# magspoof.net
KiCad netlist of a schematic drawn in EAGLE
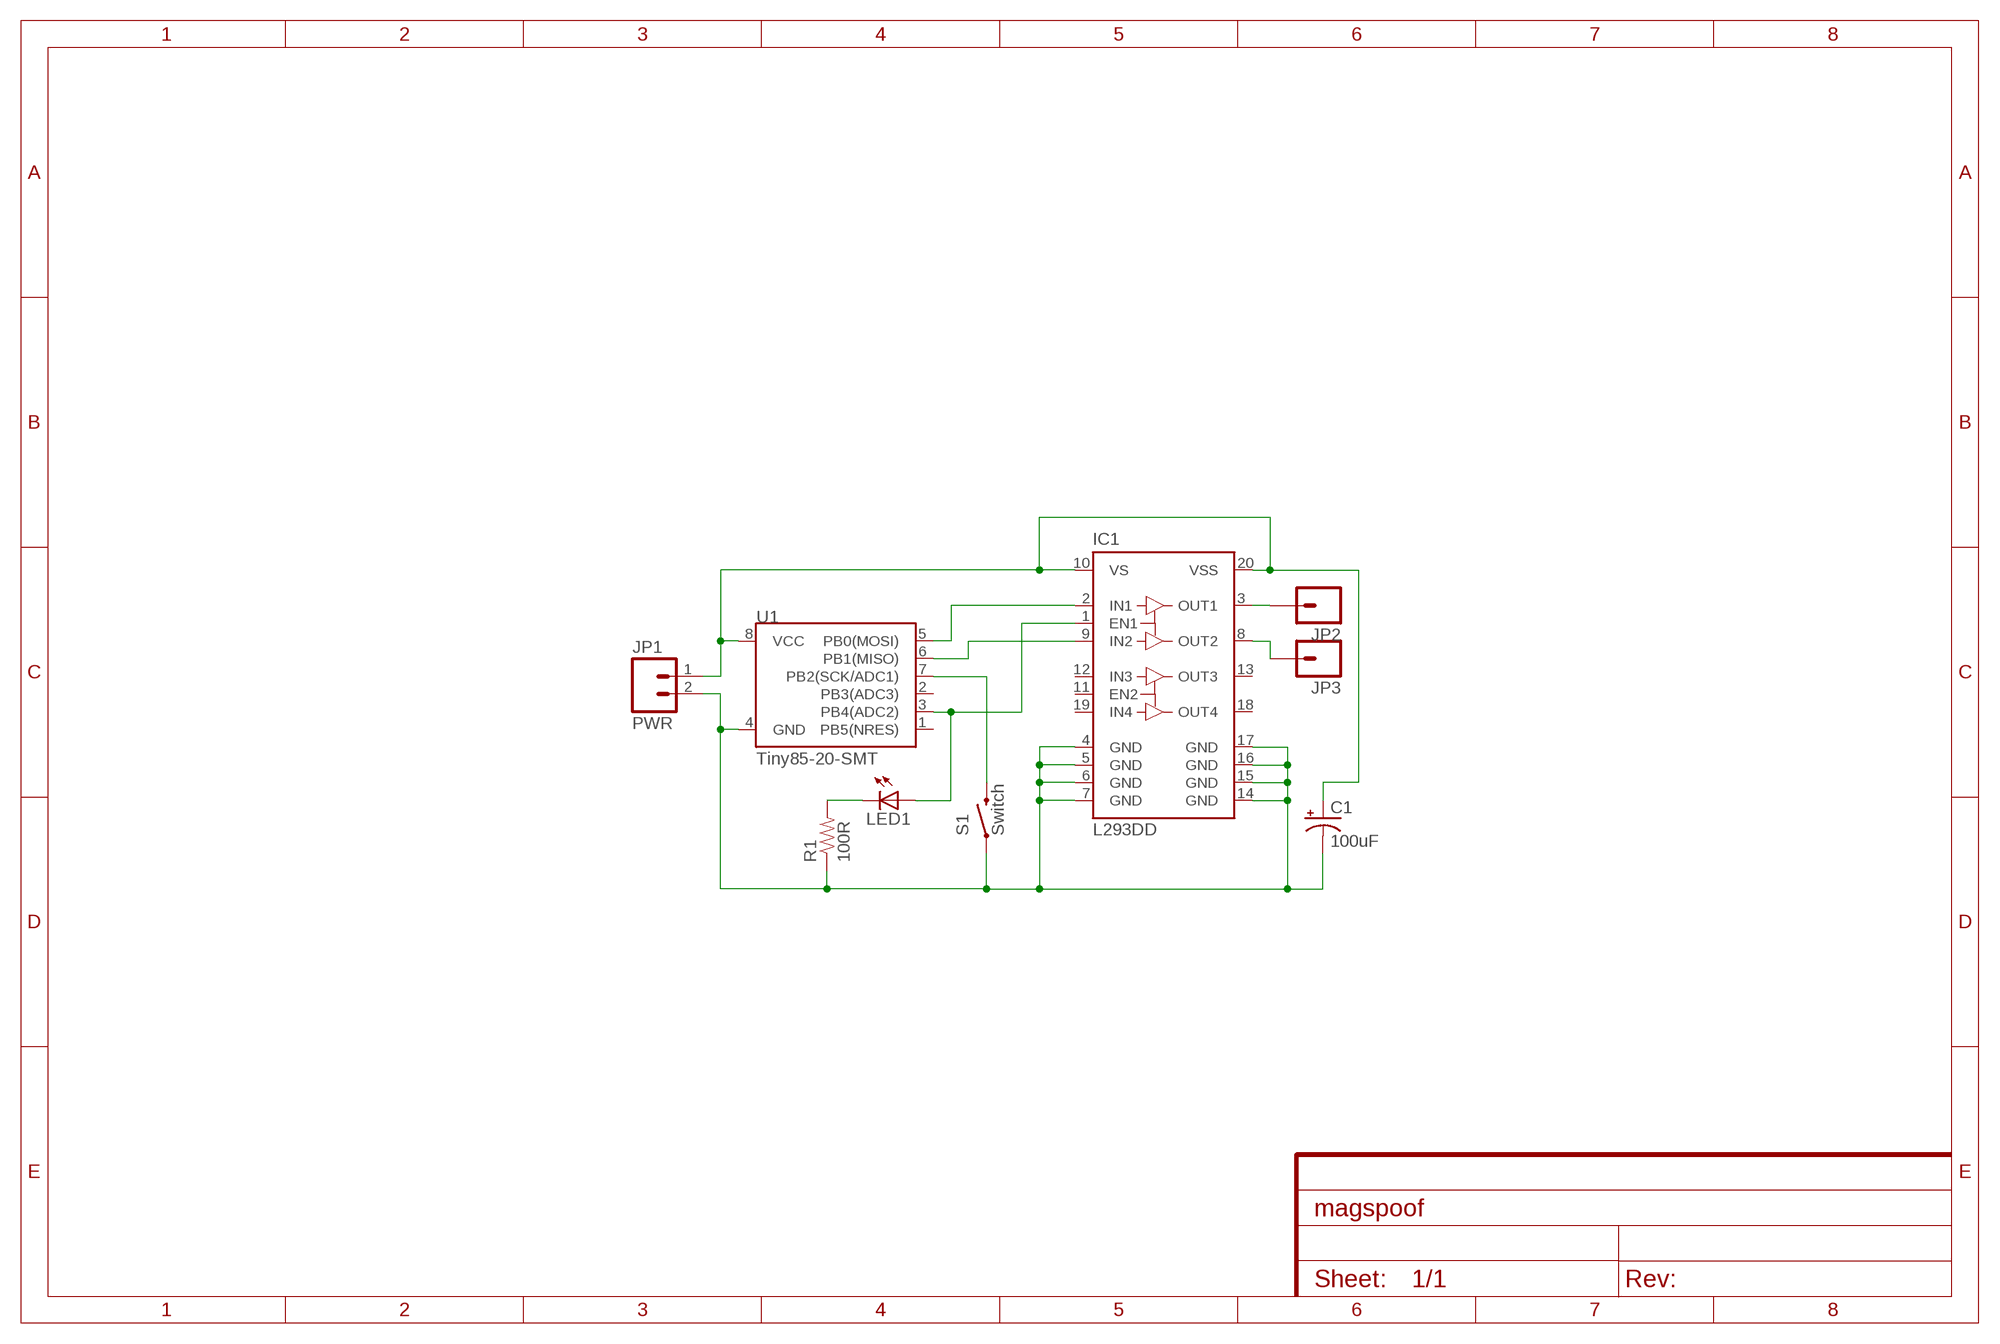
[diagram p0: schematic, sheet 1]

(export (version "E")
  (design (tool "Eeschema 10.0.6"))
  (components
    (comp (ref "C1")
      (value "100uF")
      (footprint "eagle-import:NIC_10X10.5_CAP")
      (libsource (lib "eagle-import") (part "100UF-63V-20%(ELECT)"))
    )
    (comp (ref "IC1")
      (value "L293DD")
      (footprint "eagle-import:SO20")
      (libsource (lib "eagle-import") (part "L293DD"))
    )
    (comp (ref "JP1")
      (value "PWR")
      (footprint "eagle-import:JST-2-SMD")
      (libsource (lib "eagle-import") (part "M02-JST-2MM-SMT"))
    )
    (comp (ref "JP2")
      (value "M01SMDNS")
      (footprint "eagle-import:1X01NS")
      (libsource (lib "eagle-import") (part "M01SMDNS"))
    )
    (comp (ref "JP3")
      (value "M01SMDNS")
      (footprint "eagle-import:1X01NS")
      (libsource (lib "eagle-import") (part "M01SMDNS"))
    )
    (comp (ref "LED1")
      (value "LEDCHIP-LED0805")
      (footprint "eagle-import:CHIP-LED0805")
      (libsource (lib "eagle-import") (part "LEDCHIP-LED0805"))
    )
    (comp (ref "R1")
      (value "100R")
      (footprint "eagle-import:0603-RES")
      (libsource (lib "eagle-import") (part "RESISTOR0603-RES"))
    )
    (comp (ref "S1")
      (value "Switch")
      (footprint "eagle-import:TACTILE-SWITCH-SMD")
      (libsource (lib "eagle-import") (part "SWITCH-MOMENTARY-2SMD-REDUNDANT"))
    )
    (comp (ref "U1")
      (value "Tiny85-20-SMT")
      (footprint "eagle-import:SO08-EIAJ")
      (libsource (lib "eagle-import") (part "ATTINY45TINY85-20-SMT"))
    )
  )
  (nets
    (net (code "1") (name "Net-(IC1-EN1)") (class "Default")
      (node (ref "IC1") (pin "1") (pinfunction "EN1_1") (pintype "input"))
      (node (ref "LED1") (pin "A") (pinfunction "A_A") (pintype "passive"))
      (node (ref "U1") (pin "3") (pinfunction "PB4(ADC2)_3") (pintype "bidirectional"))
    )
    (net (code "2") (name "Net-(IC1-IN1)") (class "Default")
      (node (ref "IC1") (pin "2") (pinfunction "IN1_2") (pintype "input"))
      (node (ref "U1") (pin "5") (pinfunction "PB0(MOSI)_5") (pintype "bidirectional"))
    )
    (net (code "3") (name "Net-(IC1-IN2)") (class "Default")
      (node (ref "IC1") (pin "9") (pinfunction "IN2_9") (pintype "input"))
      (node (ref "U1") (pin "6") (pinfunction "PB1(MISO)_6") (pintype "bidirectional"))
    )
    (net (code "4") (name "Net-(IC1-OUT1)") (class "Default")
      (node (ref "IC1") (pin "3") (pinfunction "OUT1_3") (pintype "output"))
      (node (ref "JP2") (pin "1") (pinfunction "1_1") (pintype "passive"))
    )
    (net (code "5") (name "Net-(IC1-OUT2)") (class "Default")
      (node (ref "IC1") (pin "8") (pinfunction "OUT2_8") (pintype "output"))
      (node (ref "JP3") (pin "1") (pinfunction "1_1") (pintype "passive"))
    )
    (net (code "6") (name "Net-(IC1-VS)") (class "Default")
      (node (ref "C1") (pin "+") (pinfunction "+_+") (pintype "passive"))
      (node (ref "IC1") (pin "10") (pinfunction "VS_10") (pintype "power_in"))
      (node (ref "IC1") (pin "20") (pinfunction "VSS_20") (pintype "power_in"))
      (node (ref "JP1") (pin "1") (pinfunction "2_1") (pintype "passive"))
      (node (ref "U1") (pin "8") (pinfunction "VCC_8") (pintype "bidirectional"))
    )
    (net (code "7") (name "Net-(JP1-1)") (class "Default")
      (node (ref "C1") (pin "-") (pinfunction "-_-") (pintype "passive"))
      (node (ref "IC1") (pin "14") (pinfunction "GND_14") (pintype "power_in"))
      (node (ref "IC1") (pin "15") (pinfunction "GND_15") (pintype "power_in"))
      (node (ref "IC1") (pin "16") (pinfunction "GND_16") (pintype "power_in"))
      (node (ref "IC1") (pin "17") (pinfunction "GND_17") (pintype "power_in"))
      (node (ref "IC1") (pin "4") (pinfunction "GND_4") (pintype "power_in"))
      (node (ref "IC1") (pin "5") (pinfunction "GND_5") (pintype "power_in"))
      (node (ref "IC1") (pin "6") (pinfunction "GND_6") (pintype "power_in"))
      (node (ref "IC1") (pin "7") (pinfunction "GND_7") (pintype "power_in"))
      (node (ref "JP1") (pin "2") (pinfunction "1_2") (pintype "passive"))
      (node (ref "R1") (pin "1") (pinfunction "1_1") (pintype "passive"))
      (node (ref "S1") (pin "1") (pinfunction "1_1") (pintype "passive"))
      (node (ref "S1") (pin "2") (pinfunction "1_2") (pintype "passive"))
      (node (ref "U1") (pin "4") (pinfunction "GND_4") (pintype "bidirectional"))
    )
    (net (code "8") (name "Net-(LED1-PadC)") (class "Default")
      (node (ref "LED1") (pin "C") (pinfunction "C_C") (pintype "passive"))
      (node (ref "R1") (pin "2") (pinfunction "2_2") (pintype "passive"))
    )
    (net (code "9") (name "Net-(U1-PB2(SCK{slash}ADC1))") (class "Default")
      (node (ref "S1") (pin "3") (pinfunction "2_3") (pintype "passive"))
      (node (ref "S1") (pin "4") (pinfunction "2_4") (pintype "passive"))
      (node (ref "U1") (pin "7") (pinfunction "PB2(SCK/ADC1)_7") (pintype "bidirectional"))
    )
    (net (code "10") (name "unconnected-(IC1-EN2-Pad11)") (class "Default")
      (node (ref "IC1") (pin "11") (pinfunction "EN2_11") (pintype "input"))
    )
    (net (code "11") (name "unconnected-(IC1-IN3-Pad12)") (class "Default")
      (node (ref "IC1") (pin "12") (pinfunction "IN3_12") (pintype "input"))
    )
    (net (code "12") (name "unconnected-(IC1-IN4-Pad19)") (class "Default")
      (node (ref "IC1") (pin "19") (pinfunction "IN4_19") (pintype "input"))
    )
    (net (code "13") (name "unconnected-(IC1-OUT3-Pad13)") (class "Default")
      (node (ref "IC1") (pin "13") (pinfunction "OUT3_13") (pintype "output"))
    )
    (net (code "14") (name "unconnected-(IC1-OUT4-Pad18)") (class "Default")
      (node (ref "IC1") (pin "18") (pinfunction "OUT4_18") (pintype "output"))
    )
    (net (code "15") (name "unconnected-(U1-PB3(ADC3)-Pad2)") (class "Default")
      (node (ref "U1") (pin "2") (pinfunction "PB3(ADC3)_2") (pintype "bidirectional"))
    )
    (net (code "16") (name "unconnected-(U1-PB5(NRES)-Pad1)") (class "Default")
      (node (ref "U1") (pin "1") (pinfunction "PB5(NRES)_1") (pintype "bidirectional"))
    )
  )
)
